# controller4.net
KiCad netlist of a schematic drawn in EAGLE
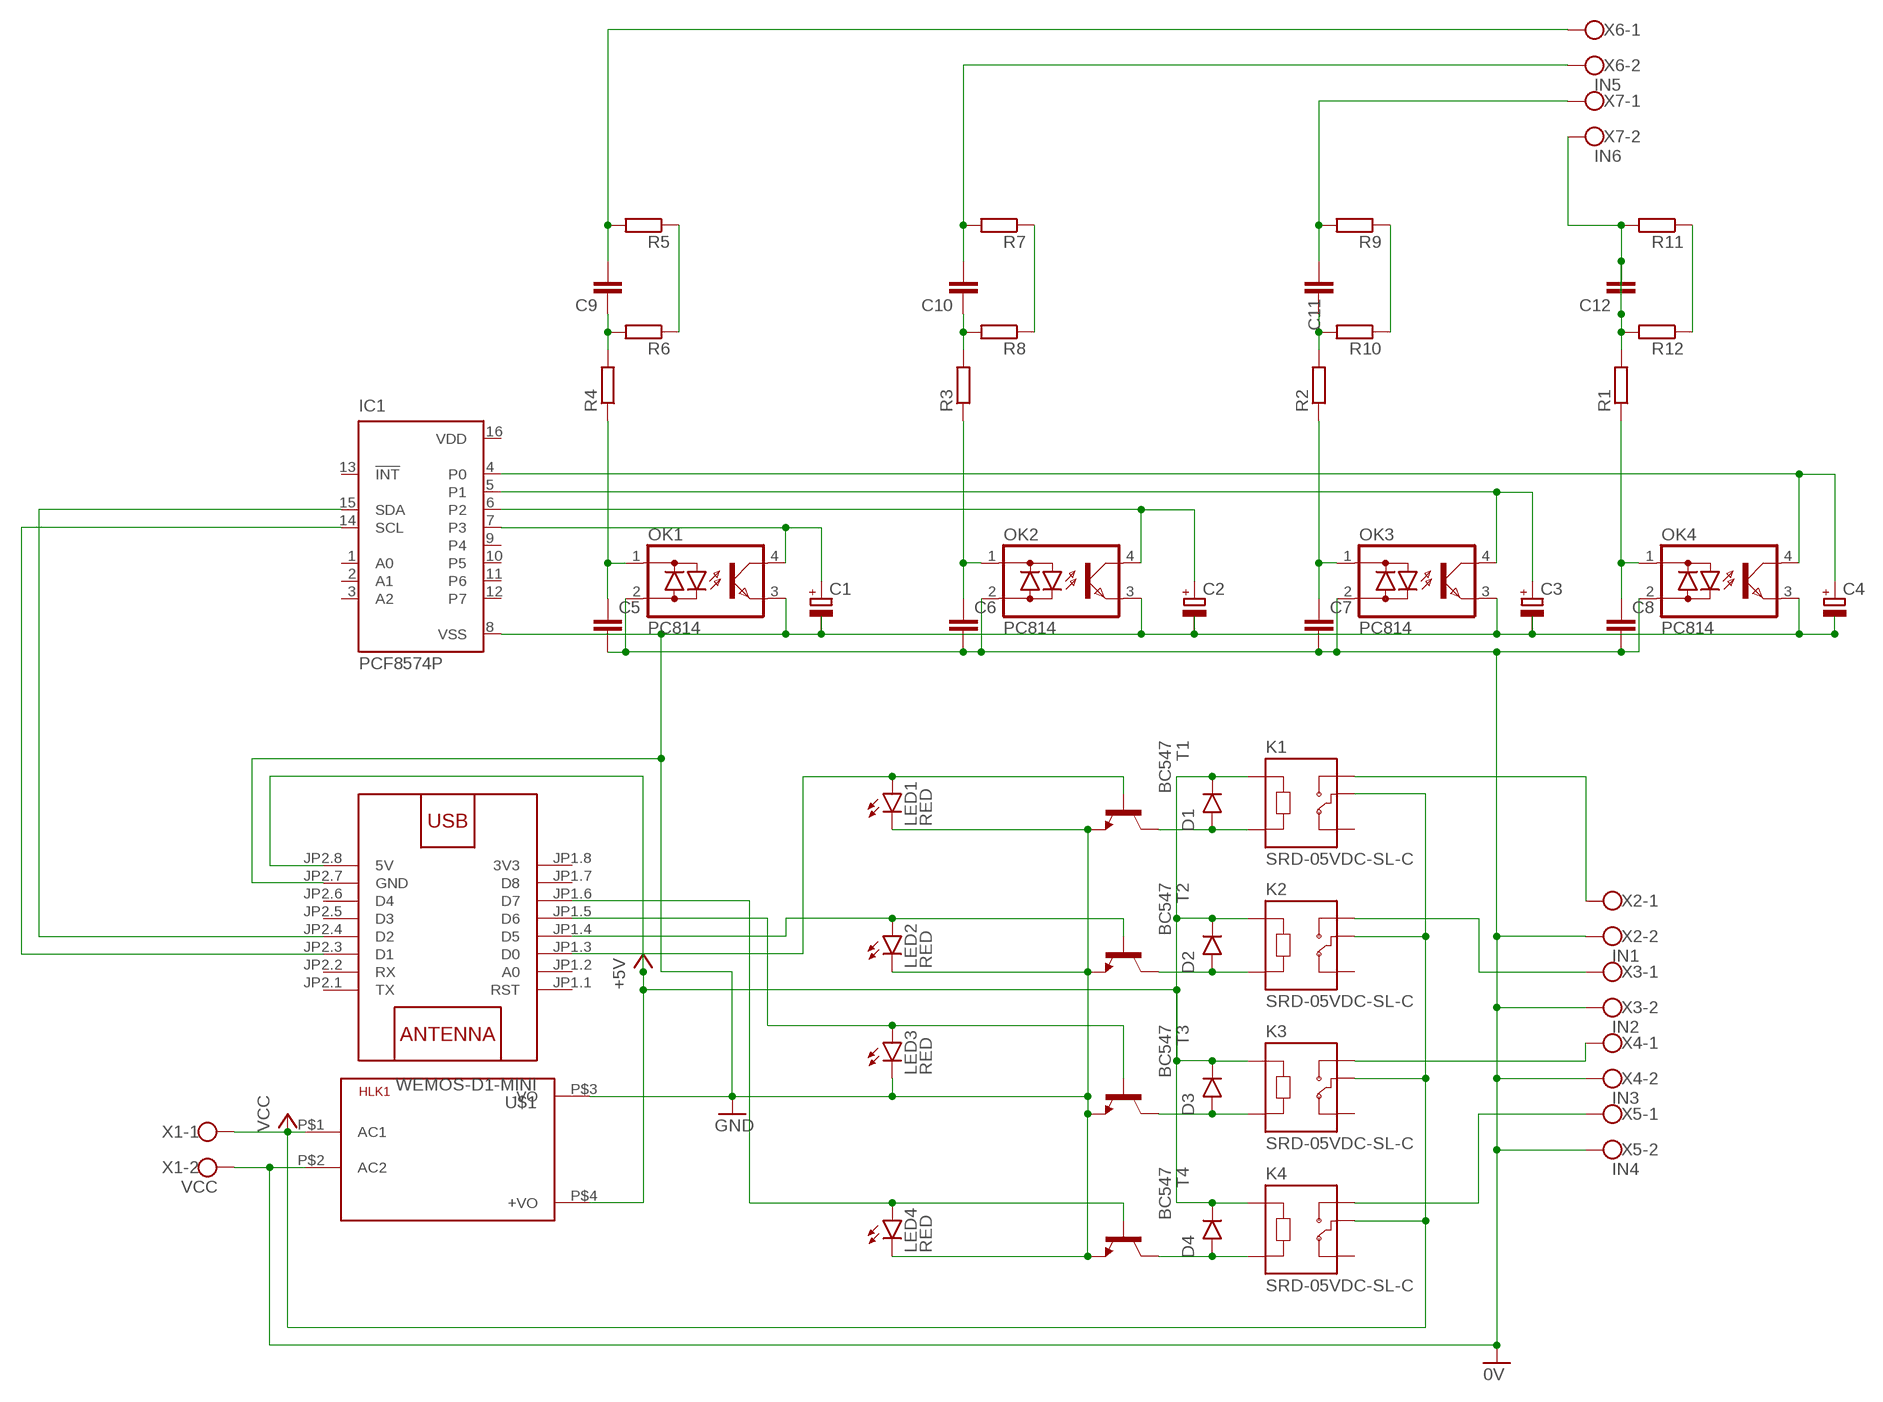
[diagram p0: schematic, sheet 1]

(export (version "E")
  (design (tool "Eeschema 10.0.6"))
  (components
    (comp (ref "C1")
      (value "CPOL-EUE5-5")
      (footprint "eagle-import:E5-5")
      (libsource (lib "eagle-import") (part "CPOL-EUE5-5"))
    )
    (comp (ref "C2")
      (value "CPOL-EUE5-5")
      (footprint "eagle-import:E5-5")
      (libsource (lib "eagle-import") (part "CPOL-EUE5-5"))
    )
    (comp (ref "C3")
      (value "CPOL-EUE5-5")
      (footprint "eagle-import:E5-5")
      (libsource (lib "eagle-import") (part "CPOL-EUE5-5"))
    )
    (comp (ref "C4")
      (value "CPOL-EUE5-5")
      (footprint "eagle-import:E5-5")
      (libsource (lib "eagle-import") (part "CPOL-EUE5-5"))
    )
    (comp (ref "C5")
      (value "C-EU025-024X044")
      (footprint "eagle-import:C025-024X044")
      (libsource (lib "eagle-import") (part "C-EU025-024X044"))
    )
    (comp (ref "C6")
      (value "C-EU025-024X044")
      (footprint "eagle-import:C025-024X044")
      (libsource (lib "eagle-import") (part "C-EU025-024X044"))
    )
    (comp (ref "C7")
      (value "C-EU025-024X044")
      (footprint "eagle-import:C025-024X044")
      (libsource (lib "eagle-import") (part "C-EU025-024X044"))
    )
    (comp (ref "C8")
      (value "C-EU025-024X044")
      (footprint "eagle-import:C025-024X044")
      (libsource (lib "eagle-import") (part "C-EU025-024X044"))
    )
    (comp (ref "C9")
      (value "C-EU025-024X044")
      (footprint "eagle-import:C025-024X044")
      (libsource (lib "eagle-import") (part "C-EU025-024X044"))
    )
    (comp (ref "C10")
      (value "C-EU025-024X044")
      (footprint "eagle-import:C025-024X044")
      (libsource (lib "eagle-import") (part "C-EU025-024X044"))
    )
    (comp (ref "C11")
      (value "C-EU025-024X044")
      (footprint "eagle-import:C025-024X044")
      (libsource (lib "eagle-import") (part "C-EU025-024X044"))
    )
    (comp (ref "C12")
      (value "C-EU025-024X044")
      (footprint "eagle-import:C025-024X044")
      (libsource (lib "eagle-import") (part "C-EU025-024X044"))
    )
    (comp (ref "D1")
      (value "1N4001")
      (footprint "eagle-import:DO41-10")
      (libsource (lib "eagle-import") (part "1N4001"))
    )
    (comp (ref "D2")
      (value "1N4001")
      (footprint "eagle-import:DO41-10")
      (libsource (lib "eagle-import") (part "1N4001"))
    )
    (comp (ref "D3")
      (value "1N4001")
      (footprint "eagle-import:DO41-10")
      (libsource (lib "eagle-import") (part "1N4001"))
    )
    (comp (ref "D4")
      (value "1N4001")
      (footprint "eagle-import:DO41-10")
      (libsource (lib "eagle-import") (part "1N4001"))
    )
    (comp (ref "HLK1")
      (value "HLK-PM013W")
      (footprint "eagle-import:HLK-PM01")
      (libsource (lib "eagle-import") (part "HLK-PM013W"))
    )
    (comp (ref "IC1")
      (value "PCF8574P")
      (footprint "eagle-import:DIL16")
      (fields (field (name "MPN") "PCF8574PN"))
      (libsource (lib "eagle-import") (part "PCF8574P"))
    )
    (comp (ref "K1")
      (value "SRD-05VDC-SL-C")
      (footprint "eagle-import:RELAY_SRD-05VDC-SL-C")
      (fields (field (name "MF") "Songle Relay"))
      (libsource (lib "eagle-import") (part "SRD-05VDC-SL-C"))
    )
    (comp (ref "K2")
      (value "SRD-05VDC-SL-C")
      (footprint "eagle-import:RELAY_SRD-05VDC-SL-C")
      (fields (field (name "MF") "Songle Relay"))
      (libsource (lib "eagle-import") (part "SRD-05VDC-SL-C"))
    )
    (comp (ref "K3")
      (value "SRD-05VDC-SL-C")
      (footprint "eagle-import:RELAY_SRD-05VDC-SL-C")
      (fields (field (name "MF") "Songle Relay"))
      (libsource (lib "eagle-import") (part "SRD-05VDC-SL-C"))
    )
    (comp (ref "K4")
      (value "SRD-05VDC-SL-C")
      (footprint "eagle-import:RELAY_SRD-05VDC-SL-C")
      (fields (field (name "MF") "Songle Relay"))
      (libsource (lib "eagle-import") (part "SRD-05VDC-SL-C"))
    )
    (comp (ref "LED1")
      (value "RED")
      (footprint "eagle-import:LED3MM")
      (libsource (lib "eagle-import") (part "LED3MM"))
    )
    (comp (ref "LED2")
      (value "RED")
      (footprint "eagle-import:LED3MM")
      (libsource (lib "eagle-import") (part "LED3MM"))
    )
    (comp (ref "LED3")
      (value "RED")
      (footprint "eagle-import:LED3MM")
      (libsource (lib "eagle-import") (part "LED3MM"))
    )
    (comp (ref "LED4")
      (value "RED")
      (footprint "eagle-import:LED3MM")
      (libsource (lib "eagle-import") (part "LED3MM"))
    )
    (comp (ref "OK1")
      (value "PC814")
      (footprint "eagle-import:DIL04")
      (libsource (lib "eagle-import") (part "PC814"))
    )
    (comp (ref "OK2")
      (value "PC814")
      (footprint "eagle-import:DIL04")
      (libsource (lib "eagle-import") (part "PC814"))
    )
    (comp (ref "OK3")
      (value "PC814")
      (footprint "eagle-import:DIL04")
      (libsource (lib "eagle-import") (part "PC814"))
    )
    (comp (ref "OK4")
      (value "PC814")
      (footprint "eagle-import:DIL04")
      (libsource (lib "eagle-import") (part "PC814"))
    )
    (comp (ref "R1")
      (value "R-EU_0204/5")
      (footprint "eagle-import:0204_5")
      (libsource (lib "eagle-import") (part "R-EU_0204/5"))
    )
    (comp (ref "R2")
      (value "R-EU_0204/5")
      (footprint "eagle-import:0204_5")
      (libsource (lib "eagle-import") (part "R-EU_0204/5"))
    )
    (comp (ref "R3")
      (value "R-EU_0204/5")
      (footprint "eagle-import:0204_5")
      (libsource (lib "eagle-import") (part "R-EU_0204/5"))
    )
    (comp (ref "R4")
      (value "R-EU_0204/5")
      (footprint "eagle-import:0204_5")
      (libsource (lib "eagle-import") (part "R-EU_0204/5"))
    )
    (comp (ref "R5")
      (value "R-EU_0204/5")
      (footprint "eagle-import:0204_5")
      (libsource (lib "eagle-import") (part "R-EU_0204/5"))
    )
    (comp (ref "R6")
      (value "R-EU_0204/5")
      (footprint "eagle-import:0204_5")
      (libsource (lib "eagle-import") (part "R-EU_0204/5"))
    )
    (comp (ref "R7")
      (value "R-EU_0204/5")
      (footprint "eagle-import:0204_5")
      (libsource (lib "eagle-import") (part "R-EU_0204/5"))
    )
    (comp (ref "R8")
      (value "R-EU_0204/5")
      (footprint "eagle-import:0204_5")
      (libsource (lib "eagle-import") (part "R-EU_0204/5"))
    )
    (comp (ref "R9")
      (value "R-EU_0204/5")
      (footprint "eagle-import:0204_5")
      (libsource (lib "eagle-import") (part "R-EU_0204/5"))
    )
    (comp (ref "R10")
      (value "R-EU_0204/5")
      (footprint "eagle-import:0204_5")
      (libsource (lib "eagle-import") (part "R-EU_0204/5"))
    )
    (comp (ref "R11")
      (value "R-EU_0204/5")
      (footprint "eagle-import:0204_5")
      (libsource (lib "eagle-import") (part "R-EU_0204/5"))
    )
    (comp (ref "R12")
      (value "R-EU_0204/5")
      (footprint "eagle-import:0204_5")
      (libsource (lib "eagle-import") (part "R-EU_0204/5"))
    )
    (comp (ref "T1")
      (value "BC547")
      (footprint "eagle-import:TO92")
      (libsource (lib "eagle-import") (part "BC547"))
    )
    (comp (ref "T2")
      (value "BC547")
      (footprint "eagle-import:TO92")
      (libsource (lib "eagle-import") (part "BC547"))
    )
    (comp (ref "T3")
      (value "BC547")
      (footprint "eagle-import:TO92")
      (libsource (lib "eagle-import") (part "BC547"))
    )
    (comp (ref "T4")
      (value "BC547")
      (footprint "eagle-import:TO92")
      (libsource (lib "eagle-import") (part "BC547"))
    )
    (comp (ref "U$1")
      (value "WEMOS-D1-MINI")
      (footprint "eagle-import:WEMOS-D1-MINI")
      (libsource (lib "eagle-import") (part "WEMOS-D1-MINI"))
    )
    (comp (ref "X1")
      (value "VCC")
      (footprint "eagle-import:W237-102")
      (fields (field (name "MPN") "237-102"))
      (libsource (lib "eagle-import") (part "W237-102"))
    )
    (comp (ref "X2")
      (value "IN1")
      (footprint "eagle-import:W237-102")
      (fields (field (name "MPN") "237-102"))
      (libsource (lib "eagle-import") (part "W237-102"))
    )
    (comp (ref "X3")
      (value "IN2")
      (footprint "eagle-import:W237-102")
      (fields (field (name "MPN") "237-102"))
      (libsource (lib "eagle-import") (part "W237-102"))
    )
    (comp (ref "X4")
      (value "IN3")
      (footprint "eagle-import:W237-102")
      (fields (field (name "MPN") "237-102"))
      (libsource (lib "eagle-import") (part "W237-102"))
    )
    (comp (ref "X5")
      (value "IN4")
      (footprint "eagle-import:W237-102")
      (fields (field (name "MPN") "237-102"))
      (libsource (lib "eagle-import") (part "W237-102"))
    )
    (comp (ref "X6")
      (value "IN5")
      (footprint "eagle-import:W237-102")
      (fields (field (name "MPN") "237-102"))
      (libsource (lib "eagle-import") (part "W237-102"))
    )
    (comp (ref "X7")
      (value "IN6")
      (footprint "eagle-import:W237-102")
      (fields (field (name "MPN") "237-102"))
      (libsource (lib "eagle-import") (part "W237-102"))
    )
  )
  (nets
    (net (code "1") (name "+5V") (class "Default")
      (node (ref "D1") (pin "C") (pinfunction "CATHODE_C") (pintype "passive"))
      (node (ref "D2") (pin "C") (pinfunction "CATHODE_C") (pintype "passive"))
      (node (ref "D3") (pin "C") (pinfunction "CATHODE_C") (pintype "passive"))
      (node (ref "D4") (pin "C") (pinfunction "CATHODE_C") (pintype "passive"))
      (node (ref "HLK1") (pin "P$4") (pinfunction "+VO_P$4") (pintype "bidirectional"))
      (node (ref "K1") (pin "A1") (pinfunction "A1_A1") (pintype "passive"))
      (node (ref "K2") (pin "A1") (pinfunction "A1_A1") (pintype "passive"))
      (node (ref "K3") (pin "A1") (pinfunction "A1_A1") (pintype "passive"))
      (node (ref "K4") (pin "A1") (pinfunction "A1_A1") (pintype "passive"))
      (node (ref "U$1") (pin "JP2.8") (pinfunction "5V_JP2.8") (pintype "power_in"))
    )
    (net (code "2") (name "/3V3") (class "Default")
      (node (ref "U$1") (pin "JP1.8") (pinfunction "3V3_JP1.8") (pintype "power_in"))
    )
    (net (code "3") (name "/VDD") (class "Default")
      (node (ref "IC1") (pin "16") (pinfunction "VDD_16") (pintype "power_in"))
    )
    (net (code "4") (name "0V") (class "Default")
      (node (ref "C5") (pin "2") (pinfunction "2_2") (pintype "passive"))
      (node (ref "C6") (pin "2") (pinfunction "2_2") (pintype "passive"))
      (node (ref "C7") (pin "2") (pinfunction "2_2") (pintype "passive"))
      (node (ref "C8") (pin "2") (pinfunction "2_2") (pintype "passive"))
      (node (ref "HLK1") (pin "P$2") (pinfunction "AC2_P$2") (pintype "bidirectional"))
      (node (ref "OK1") (pin "2") (pinfunction "AC2_2") (pintype "passive"))
      (node (ref "OK2") (pin "2") (pinfunction "AC2_2") (pintype "passive"))
      (node (ref "OK3") (pin "2") (pinfunction "AC2_2") (pintype "passive"))
      (node (ref "OK4") (pin "2") (pinfunction "AC2_2") (pintype "passive"))
      (node (ref "X1") (pin "2") (pinfunction "KL_2") (pintype "passive"))
      (node (ref "X2") (pin "2") (pinfunction "KL_2") (pintype "passive"))
      (node (ref "X3") (pin "2") (pinfunction "KL_2") (pintype "passive"))
      (node (ref "X4") (pin "2") (pinfunction "KL_2") (pintype "passive"))
      (node (ref "X5") (pin "2") (pinfunction "KL_2") (pintype "passive"))
    )
    (net (code "5") (name "GND") (class "Default")
      (node (ref "C1") (pin "-") (pinfunction "-_-") (pintype "passive"))
      (node (ref "C2") (pin "-") (pinfunction "-_-") (pintype "passive"))
      (node (ref "C3") (pin "-") (pinfunction "-_-") (pintype "passive"))
      (node (ref "C4") (pin "-") (pinfunction "-_-") (pintype "passive"))
      (node (ref "HLK1") (pin "P$3") (pinfunction "-VO_P$3") (pintype "bidirectional"))
      (node (ref "IC1") (pin "8") (pinfunction "VSS_8") (pintype "power_in"))
      (node (ref "LED1") (pin "K") (pinfunction "C_K") (pintype "passive"))
      (node (ref "LED2") (pin "K") (pinfunction "C_K") (pintype "passive"))
      (node (ref "LED3") (pin "K") (pinfunction "C_K") (pintype "passive"))
      (node (ref "LED4") (pin "K") (pinfunction "C_K") (pintype "passive"))
      (node (ref "OK1") (pin "3") (pinfunction "E_3") (pintype "passive"))
      (node (ref "OK2") (pin "3") (pinfunction "E_3") (pintype "passive"))
      (node (ref "OK3") (pin "3") (pinfunction "E_3") (pintype "passive"))
      (node (ref "OK4") (pin "3") (pinfunction "E_3") (pintype "passive"))
      (node (ref "T1") (pin "1") (pinfunction "E_1") (pintype "passive"))
      (node (ref "T2") (pin "1") (pinfunction "E_1") (pintype "passive"))
      (node (ref "T3") (pin "1") (pinfunction "E_1") (pintype "passive"))
      (node (ref "T4") (pin "1") (pinfunction "E_1") (pintype "passive"))
      (node (ref "U$1") (pin "JP2.7") (pinfunction "GND_JP2.7") (pintype "power_in"))
    )
    (net (code "6") (name "Net-(C9-Pad1)") (class "Default")
      (node (ref "C9") (pin "1") (pinfunction "1_1") (pintype "passive"))
      (node (ref "R4") (pin "2") (pinfunction "2_2") (pintype "passive"))
      (node (ref "R6") (pin "2") (pinfunction "2_2") (pintype "passive"))
    )
    (net (code "7") (name "Net-(C10-Pad1)") (class "Default")
      (node (ref "C10") (pin "1") (pinfunction "1_1") (pintype "passive"))
      (node (ref "R3") (pin "2") (pinfunction "2_2") (pintype "passive"))
      (node (ref "R8") (pin "2") (pinfunction "2_2") (pintype "passive"))
    )
    (net (code "8") (name "Net-(C11-Pad1)") (class "Default")
      (node (ref "C11") (pin "1") (pinfunction "1_1") (pintype "passive"))
      (node (ref "R10") (pin "2") (pinfunction "2_2") (pintype "passive"))
      (node (ref "R2") (pin "2") (pinfunction "2_2") (pintype "passive"))
    )
    (net (code "9") (name "Net-(D1-ANODE)") (class "Default")
      (node (ref "D1") (pin "A") (pinfunction "ANODE_A") (pintype "passive"))
      (node (ref "K1") (pin "A2") (pinfunction "A2_A2") (pintype "passive"))
      (node (ref "T1") (pin "3") (pinfunction "C_3") (pintype "passive"))
    )
    (net (code "10") (name "Net-(D2-ANODE)") (class "Default")
      (node (ref "D2") (pin "A") (pinfunction "ANODE_A") (pintype "passive"))
      (node (ref "K2") (pin "A2") (pinfunction "A2_A2") (pintype "passive"))
      (node (ref "T2") (pin "3") (pinfunction "C_3") (pintype "passive"))
    )
    (net (code "11") (name "Net-(D3-ANODE)") (class "Default")
      (node (ref "D3") (pin "A") (pinfunction "ANODE_A") (pintype "passive"))
      (node (ref "K3") (pin "A2") (pinfunction "A2_A2") (pintype "passive"))
      (node (ref "T3") (pin "3") (pinfunction "C_3") (pintype "passive"))
    )
    (net (code "12") (name "Net-(D4-ANODE)") (class "Default")
      (node (ref "D4") (pin "A") (pinfunction "ANODE_A") (pintype "passive"))
      (node (ref "K4") (pin "A2") (pinfunction "A2_A2") (pintype "passive"))
      (node (ref "T4") (pin "3") (pinfunction "C_3") (pintype "passive"))
    )
    (net (code "13") (name "Net-(IC1-P0)") (class "Default")
      (node (ref "C4") (pin "+") (pinfunction "+_+") (pintype "passive"))
      (node (ref "IC1") (pin "4") (pinfunction "P0_4") (pintype "bidirectional"))
      (node (ref "OK4") (pin "4") (pinfunction "C_4") (pintype "passive"))
    )
    (net (code "14") (name "Net-(IC1-P1)") (class "Default")
      (node (ref "C3") (pin "+") (pinfunction "+_+") (pintype "passive"))
      (node (ref "IC1") (pin "5") (pinfunction "P1_5") (pintype "bidirectional"))
      (node (ref "OK3") (pin "4") (pinfunction "C_4") (pintype "passive"))
    )
    (net (code "15") (name "Net-(IC1-P2)") (class "Default")
      (node (ref "C2") (pin "+") (pinfunction "+_+") (pintype "passive"))
      (node (ref "IC1") (pin "6") (pinfunction "P2_6") (pintype "bidirectional"))
      (node (ref "OK2") (pin "4") (pinfunction "C_4") (pintype "passive"))
    )
    (net (code "16") (name "Net-(IC1-P3)") (class "Default")
      (node (ref "C1") (pin "+") (pinfunction "+_+") (pintype "passive"))
      (node (ref "IC1") (pin "7") (pinfunction "P3_7") (pintype "bidirectional"))
      (node (ref "OK1") (pin "4") (pinfunction "C_4") (pintype "passive"))
    )
    (net (code "17") (name "Net-(IC1-SCL)") (class "Default")
      (node (ref "IC1") (pin "14") (pinfunction "SCL_14") (pintype "input"))
      (node (ref "U$1") (pin "JP2.3") (pinfunction "D1_JP2.3") (pintype "bidirectional"))
    )
    (net (code "18") (name "Net-(IC1-SDA)") (class "Default")
      (node (ref "IC1") (pin "15") (pinfunction "SDA_15") (pintype "bidirectional"))
      (node (ref "U$1") (pin "JP2.4") (pinfunction "D2_JP2.4") (pintype "bidirectional"))
    )
    (net (code "19") (name "Net-(OK1-AC1)") (class "Default")
      (node (ref "C5") (pin "1") (pinfunction "1_1") (pintype "passive"))
      (node (ref "OK1") (pin "1") (pinfunction "AC1_1") (pintype "passive"))
      (node (ref "R4") (pin "1") (pinfunction "1_1") (pintype "passive"))
    )
    (net (code "20") (name "Net-(OK2-AC1)") (class "Default")
      (node (ref "C6") (pin "1") (pinfunction "1_1") (pintype "passive"))
      (node (ref "OK2") (pin "1") (pinfunction "AC1_1") (pintype "passive"))
      (node (ref "R3") (pin "1") (pinfunction "1_1") (pintype "passive"))
    )
    (net (code "21") (name "Net-(OK3-AC1)") (class "Default")
      (node (ref "C7") (pin "1") (pinfunction "1_1") (pintype "passive"))
      (node (ref "OK3") (pin "1") (pinfunction "AC1_1") (pintype "passive"))
      (node (ref "R2") (pin "1") (pinfunction "1_1") (pintype "passive"))
    )
    (net (code "22") (name "Net-(OK4-AC1)") (class "Default")
      (node (ref "C8") (pin "1") (pinfunction "1_1") (pintype "passive"))
      (node (ref "OK4") (pin "1") (pinfunction "AC1_1") (pintype "passive"))
      (node (ref "R1") (pin "1") (pinfunction "1_1") (pintype "passive"))
    )
    (net (code "23") (name "Net-(R5-Pad1)") (class "Default")
      (node (ref "R5") (pin "1") (pinfunction "1_1") (pintype "passive"))
      (node (ref "R6") (pin "1") (pinfunction "1_1") (pintype "passive"))
    )
    (net (code "24") (name "Net-(R7-Pad1)") (class "Default")
      (node (ref "R7") (pin "1") (pinfunction "1_1") (pintype "passive"))
      (node (ref "R8") (pin "1") (pinfunction "1_1") (pintype "passive"))
    )
    (net (code "25") (name "Net-(R10-Pad1)") (class "Default")
      (node (ref "R10") (pin "1") (pinfunction "1_1") (pintype "passive"))
      (node (ref "R9") (pin "1") (pinfunction "1_1") (pintype "passive"))
    )
    (net (code "26") (name "Net-(R11-Pad1)") (class "Default")
      (node (ref "R11") (pin "1") (pinfunction "1_1") (pintype "passive"))
      (node (ref "R12") (pin "1") (pinfunction "1_1") (pintype "passive"))
    )
    (net (code "27") (name "Net-(T1-B)") (class "Default")
      (node (ref "LED1") (pin "A") (pinfunction "A_A") (pintype "passive"))
      (node (ref "T1") (pin "2") (pinfunction "B_2") (pintype "passive"))
      (node (ref "U$1") (pin "JP1.3") (pinfunction "D0_JP1.3") (pintype "bidirectional"))
    )
    (net (code "28") (name "Net-(T2-B)") (class "Default")
      (node (ref "LED2") (pin "A") (pinfunction "A_A") (pintype "passive"))
      (node (ref "T2") (pin "2") (pinfunction "B_2") (pintype "passive"))
      (node (ref "U$1") (pin "JP1.4") (pinfunction "D5_JP1.4") (pintype "bidirectional"))
    )
    (net (code "29") (name "Net-(T3-B)") (class "Default")
      (node (ref "LED3") (pin "A") (pinfunction "A_A") (pintype "passive"))
      (node (ref "T3") (pin "2") (pinfunction "B_2") (pintype "passive"))
      (node (ref "U$1") (pin "JP1.5") (pinfunction "D6_JP1.5") (pintype "bidirectional"))
    )
    (net (code "30") (name "Net-(T4-B)") (class "Default")
      (node (ref "LED4") (pin "A") (pinfunction "A_A") (pintype "passive"))
      (node (ref "T4") (pin "2") (pinfunction "B_2") (pintype "passive"))
      (node (ref "U$1") (pin "JP1.6") (pinfunction "D7_JP1.6") (pintype "bidirectional"))
    )
    (net (code "31") (name "Net-(X2A-KL)") (class "Default")
      (node (ref "K1") (pin "NO") (pinfunction "NO_NO") (pintype "passive"))
      (node (ref "X2") (pin "1") (pinfunction "KL_1") (pintype "passive"))
    )
    (net (code "32") (name "Net-(X3A-KL)") (class "Default")
      (node (ref "K2") (pin "NO") (pinfunction "NO_NO") (pintype "passive"))
      (node (ref "X3") (pin "1") (pinfunction "KL_1") (pintype "passive"))
    )
    (net (code "33") (name "Net-(X4A-KL)") (class "Default")
      (node (ref "K3") (pin "NO") (pinfunction "NO_NO") (pintype "passive"))
      (node (ref "X4") (pin "1") (pinfunction "KL_1") (pintype "passive"))
    )
    (net (code "34") (name "Net-(X5A-KL)") (class "Default")
      (node (ref "K4") (pin "NO") (pinfunction "NO_NO") (pintype "passive"))
      (node (ref "X5") (pin "1") (pinfunction "KL_1") (pintype "passive"))
    )
    (net (code "35") (name "Net-(X6A-KL)") (class "Default")
      (node (ref "C9") (pin "2") (pinfunction "2_2") (pintype "passive"))
      (node (ref "R5") (pin "2") (pinfunction "2_2") (pintype "passive"))
      (node (ref "X6") (pin "1") (pinfunction "KL_1") (pintype "passive"))
    )
    (net (code "36") (name "Net-(X6B-KL)") (class "Default")
      (node (ref "C10") (pin "2") (pinfunction "2_2") (pintype "passive"))
      (node (ref "R7") (pin "2") (pinfunction "2_2") (pintype "passive"))
      (node (ref "X6") (pin "2") (pinfunction "KL_2") (pintype "passive"))
    )
    (net (code "37") (name "Net-(X7A-KL)") (class "Default")
      (node (ref "C11") (pin "2") (pinfunction "2_2") (pintype "passive"))
      (node (ref "R9") (pin "2") (pinfunction "2_2") (pintype "passive"))
      (node (ref "X7") (pin "1") (pinfunction "KL_1") (pintype "passive"))
    )
    (net (code "38") (name "Net-(X7B-KL)") (class "Default")
      (node (ref "C12") (pin "1") (pinfunction "1_1") (pintype "passive"))
      (node (ref "C12") (pin "2") (pinfunction "2_2") (pintype "passive"))
      (node (ref "R1") (pin "2") (pinfunction "2_2") (pintype "passive"))
      (node (ref "R11") (pin "2") (pinfunction "2_2") (pintype "passive"))
      (node (ref "R12") (pin "2") (pinfunction "2_2") (pintype "passive"))
      (node (ref "X7") (pin "2") (pinfunction "KL_2") (pintype "passive"))
    )
    (net (code "39") (name "VCC") (class "Default")
      (node (ref "HLK1") (pin "P$1") (pinfunction "AC1_P$1") (pintype "bidirectional"))
      (node (ref "K1") (pin "COM") (pinfunction "COM_COM") (pintype "passive"))
      (node (ref "K2") (pin "COM") (pinfunction "COM_COM") (pintype "passive"))
      (node (ref "K3") (pin "COM") (pinfunction "COM_COM") (pintype "passive"))
      (node (ref "K4") (pin "COM") (pinfunction "COM_COM") (pintype "passive"))
      (node (ref "X1") (pin "1") (pinfunction "KL_1") (pintype "passive"))
    )
    (net (code "40") (name "unconnected-(IC1-A0-Pad1)") (class "Default")
      (node (ref "IC1") (pin "1") (pinfunction "A0_1") (pintype "input"))
    )
    (net (code "41") (name "unconnected-(IC1-A1-Pad2)") (class "Default")
      (node (ref "IC1") (pin "2") (pinfunction "A1_2") (pintype "input"))
    )
    (net (code "42") (name "unconnected-(IC1-A2-Pad3)") (class "Default")
      (node (ref "IC1") (pin "3") (pinfunction "A2_3") (pintype "input"))
    )
    (net (code "43") (name "unconnected-(IC1-P4-Pad9)") (class "Default")
      (node (ref "IC1") (pin "9") (pinfunction "P4_9") (pintype "bidirectional"))
    )
    (net (code "44") (name "unconnected-(IC1-P5-Pad10)") (class "Default")
      (node (ref "IC1") (pin "10") (pinfunction "P5_10") (pintype "bidirectional"))
    )
    (net (code "45") (name "unconnected-(IC1-P6-Pad11)") (class "Default")
      (node (ref "IC1") (pin "11") (pinfunction "P6_11") (pintype "bidirectional"))
    )
    (net (code "46") (name "unconnected-(IC1-P7-Pad12)") (class "Default")
      (node (ref "IC1") (pin "12") (pinfunction "P7_12") (pintype "bidirectional"))
    )
    (net (code "47") (name "unconnected-(IC1-~{INT}-Pad13)") (class "Default")
      (node (ref "IC1") (pin "13") (pinfunction "~{INT}_13") (pintype "output"))
    )
    (net (code "48") (name "unconnected-(K1-PadNC)") (class "Default")
      (node (ref "K1") (pin "NC") (pinfunction "NC_NC") (pintype "passive"))
    )
    (net (code "49") (name "unconnected-(K2-PadNC)") (class "Default")
      (node (ref "K2") (pin "NC") (pinfunction "NC_NC") (pintype "passive"))
    )
    (net (code "50") (name "unconnected-(K3-PadNC)") (class "Default")
      (node (ref "K3") (pin "NC") (pinfunction "NC_NC") (pintype "passive"))
    )
    (net (code "51") (name "unconnected-(K4-PadNC)") (class "Default")
      (node (ref "K4") (pin "NC") (pinfunction "NC_NC") (pintype "passive"))
    )
    (net (code "52") (name "unconnected-(U$1-A0-PadJP1.2)") (class "Default")
      (node (ref "U$1") (pin "JP1.2") (pinfunction "A0_JP1.2") (pintype "bidirectional"))
    )
    (net (code "53") (name "unconnected-(U$1-D3-PadJP2.5)") (class "Default")
      (node (ref "U$1") (pin "JP2.5") (pinfunction "D3_JP2.5") (pintype "bidirectional"))
    )
    (net (code "54") (name "unconnected-(U$1-D4-PadJP2.6)") (class "Default")
      (node (ref "U$1") (pin "JP2.6") (pinfunction "D4_JP2.6") (pintype "bidirectional"))
    )
    (net (code "55") (name "unconnected-(U$1-D8-PadJP1.7)") (class "Default")
      (node (ref "U$1") (pin "JP1.7") (pinfunction "D8_JP1.7") (pintype "bidirectional"))
    )
    (net (code "56") (name "unconnected-(U$1-RST-PadJP1.1)") (class "Default")
      (node (ref "U$1") (pin "JP1.1") (pinfunction "RST_JP1.1") (pintype "bidirectional"))
    )
    (net (code "57") (name "unconnected-(U$1-RX-PadJP2.2)") (class "Default")
      (node (ref "U$1") (pin "JP2.2") (pinfunction "RX_JP2.2") (pintype "bidirectional"))
    )
    (net (code "58") (name "unconnected-(U$1-TX-PadJP2.1)") (class "Default")
      (node (ref "U$1") (pin "JP2.1") (pinfunction "TX_JP2.1") (pintype "bidirectional"))
    )
  )
)
